# OUT.net
KiCad netlist of a schematic drawn in Altium Designer
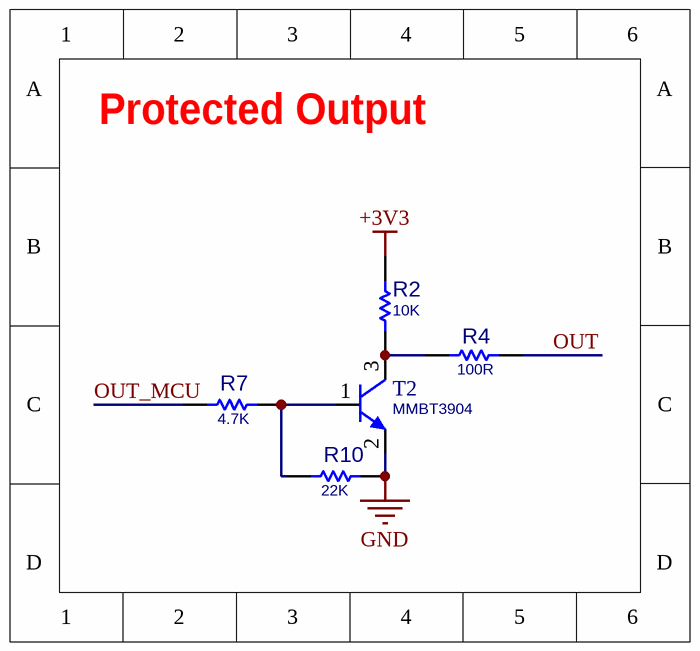
[diagram p0: OUT.SchDoc]

(export (version "E")
  (design (tool "Eeschema 10.0.6"))
  (components
    (comp (ref "R2")
      (value "10K")
      (footprint "R0603")
      (description "RES, SMD")
      (fields (field (name "MANF_P#") "RK73H1ETTP4701F") (field (name "MANF") "KOA SPEER"))
      (libsource (lib "PW Components 97_481") (part "RES_SMD"))
    )
    (comp (ref "R4")
      (value "100R")
      (footprint "R0603")
      (description "RES, SMD")
      (fields (field (name "MANF_P#") "RK73H1ETTP4701F") (field (name "MANF") "KOA SPEER"))
      (libsource (lib "PW Components 97_481") (part "RES_SMD"))
    )
    (comp (ref "R7")
      (value "4.7K")
      (footprint "R0603")
      (description "RES, SMD")
      (fields (field (name "MANF_P#") "RK73H1ETTP4701F") (field (name "MANF") "KOA SPEER"))
      (libsource (lib "PW Components 97_481") (part "RES_SMD"))
    )
    (comp (ref "R10")
      (value "22K")
      (footprint "R0603")
      (description "RES, SMD")
      (fields (field (name "MANF_P#") "RK73H1ETTP4701F") (field (name "MANF") "KOA SPEER"))
      (libsource (lib "PW Components 97_481") (part "RES_SMD"))
    )
    (comp (ref "T2")
      (value "MMBT3904")
      (footprint "SOT23_3")
      (description "BJT, NPN, 40v, 0.2A, SMD, SOT23")
      (fields (field (name "MANF") "Diodes, NXP, FAIRCHILD, ON"))
      (libsource (lib "Transistor BJT") (part "NPN_MMBT3904_SOT23"))
    )
  )
  (nets
    (net (code "1") (name "+3V3") (class "Default")
      (node (ref "R2") (pin "2") (pinfunction "2_2") (pintype "passive"))
    )
    (net (code "2") (name "/OUT") (class "Default")
      (node (ref "R4") (pin "1") (pinfunction "1_1") (pintype "passive"))
    )
    (net (code "3") (name "/OUT_MCU") (class "Default")
      (node (ref "R7") (pin "2") (pinfunction "2_2") (pintype "passive"))
    )
    (net (code "4") (name "GND") (class "Default")
      (node (ref "R10") (pin "1") (pinfunction "1_1") (pintype "passive"))
      (node (ref "T2") (pin "2") (pinfunction "E_2") (pintype "passive"))
    )
    (net (code "5") (name "Net-(T2-B)") (class "Default")
      (node (ref "R10") (pin "2") (pinfunction "2_2") (pintype "passive"))
      (node (ref "R7") (pin "1") (pinfunction "1_1") (pintype "passive"))
      (node (ref "T2") (pin "1") (pinfunction "B_1") (pintype "passive"))
    )
    (net (code "6") (name "Net-(T2-C)") (class "Default")
      (node (ref "R2") (pin "1") (pinfunction "1_1") (pintype "passive"))
      (node (ref "R4") (pin "2") (pinfunction "2_2") (pintype "passive"))
      (node (ref "T2") (pin "3") (pinfunction "C_3") (pintype "passive"))
    )
  )
)
